# battery_charger.net
KiCad netlist of a schematic drawn in Altium Designer
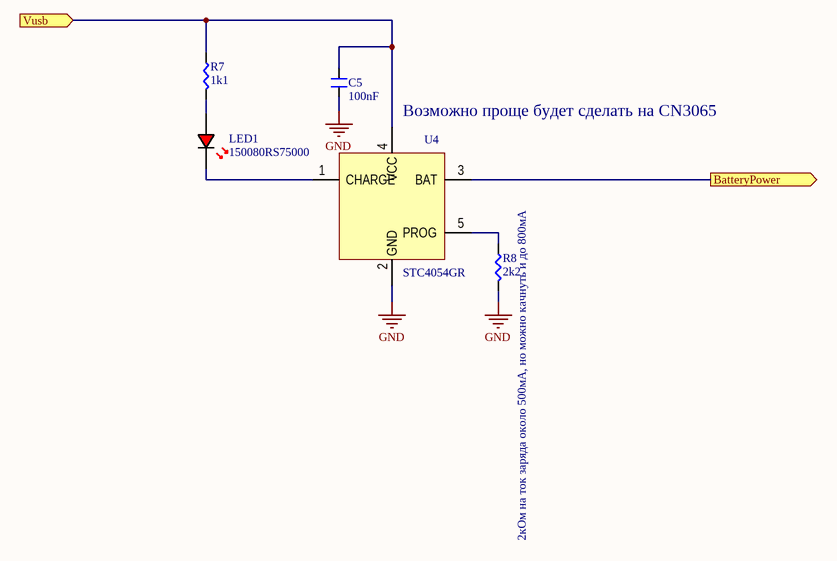
[diagram p0: battery_charger.SchDoc]

(export (version "E")
  (design (tool "Eeschema 10.0.6"))
  (components
    (comp (ref "C5")
      (value "100nF")
      (footprint "CAP0603")
      (description "Tolerance ±10%\nRated Voltage 50Vdc\nTemperature 0±30ppm/℃")
      (fields (field (name "PART NUMBER") "GCM188R71H104KA57J") (field (name "TOLERANCE") "10%"))
      (libsource (lib "Lib_Kam") (part "Capacitor"))
    )
    (comp (ref "LED1")
      (value "150080RS75000")
      (footprint "LED0805")
      (description "Standard LEDs - SMD WL-SMCW SMDMono TpVw Waterclr 0805 Red")
      (fields (field (name "MANUFACTURER") "Wurth Elektronik"))
      (libsource (lib "Lib_Kam") (part "LED (Red)"))
    )
    (comp (ref "R7")
      (value "1k1")
      (footprint "RES0603")
      (description "Tolerance ±1%\nPower (Watts) 0.1W, 1/10W\nTemperature Coefficient ±100ppm/°C")
      (fields (field (name "PART NUMBER") "ERJ-3EKF1101V") (field (name "TOLERANCE") "1%"))
      (libsource (lib "Lib_Kam") (part "Resistor"))
    )
    (comp (ref "R8")
      (value "2k2")
      (footprint "RES0603")
      (description "Tolerance ±1%\nPower (Watts) 0.1W, 1/10W\nTemperature Coefficient ±100ppm/°C")
      (fields (field (name "PART NUMBER") "541-2.20KHCT-ND") (field (name "TOLERANCE") "1%"))
      (libsource (lib "Lib_Kam") (part "Resistor"))
    )
    (comp (ref "U4")
      (value "STC4054GR")
      (footprint "SOT-23-5")
      (description "800mA Standalone linear Li-Ion\nBattery charger with thermal regulation")
      (fields (field (name "MANUFACTURER") "STMicroelectronics"))
      (libsource (lib "Lib_Kam") (part "STC4054GR"))
    )
  )
  (nets
    (net (code "1") (name "/BatteryPower") (class "Default")
      (node (ref "U4") (pin "3") (pinfunction "BAT_3") (pintype "passive"))
    )
    (net (code "2") (name "/Vusb") (class "Default")
      (node (ref "C5") (pin "2") (pinfunction "2_2") (pintype "passive"))
      (node (ref "R7") (pin "2") (pintype "passive"))
      (node (ref "U4") (pin "4") (pinfunction "VCC_4") (pintype "passive"))
    )
    (net (code "3") (name "GND") (class "Default")
      (node (ref "C5") (pin "1") (pinfunction "2_1") (pintype "passive"))
      (node (ref "R8") (pin "1") (pintype "passive"))
      (node (ref "U4") (pin "2") (pinfunction "GND_2") (pintype "passive"))
    )
    (net (code "4") (name "Net-(LED1-PadA)") (class "Default")
      (node (ref "LED1") (pin "A") (pinfunction "A_A") (pintype "passive"))
      (node (ref "R7") (pin "1") (pintype "passive"))
    )
    (net (code "5") (name "Net-(U4-CHARGE)") (class "Default")
      (node (ref "LED1") (pin "C") (pinfunction "C_C") (pintype "passive"))
      (node (ref "U4") (pin "1") (pinfunction "CHARGE_1") (pintype "passive"))
    )
    (net (code "6") (name "Net-(U4-PROG)") (class "Default")
      (node (ref "R8") (pin "2") (pintype "passive"))
      (node (ref "U4") (pin "5") (pinfunction "PROG_5") (pintype "passive"))
    )
  )
)
